# driver-power-stage.net
KiCad netlist of a schematic drawn in Altium Designer
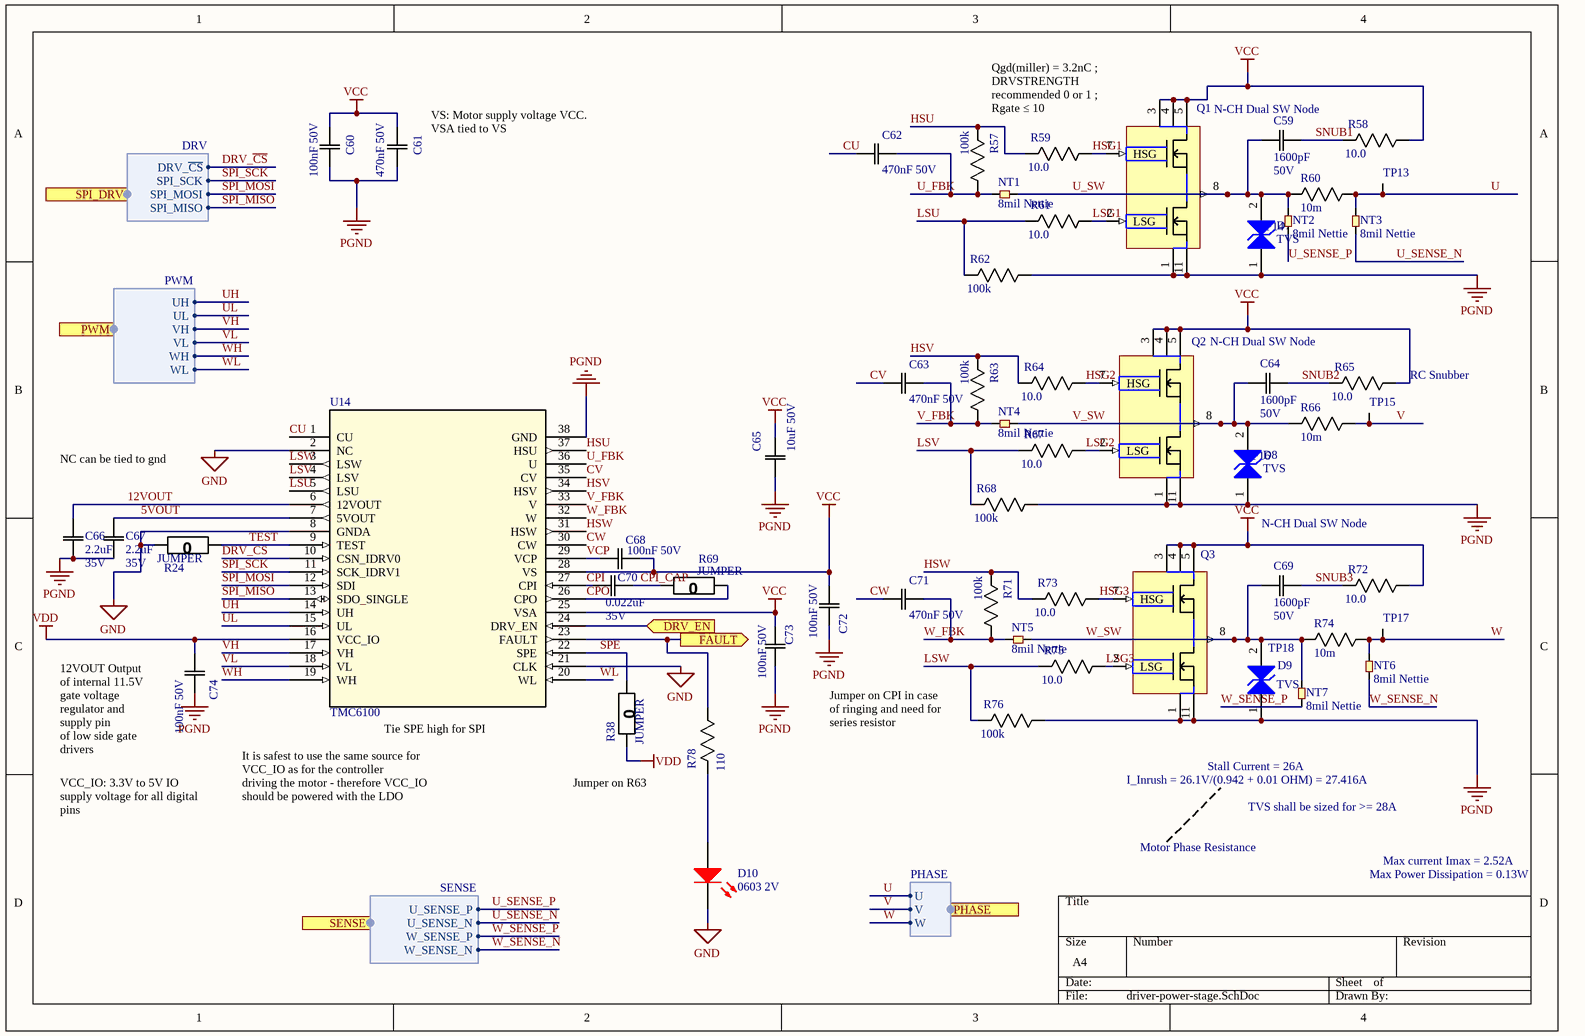
[diagram p0: driver-power-stage.SchDoc]

(export (version "E")
  (design (tool "Eeschema 10.0.6"))
  (components
    (comp (ref "C59")
      (value "1600pF")
      (footprint "0603")
      (description "Default Symbol for Capacitors")
      (fields
        (field (name "TOLERANCE") "5%")
        (field (name "RATING") "50V")
        (field (name "PART NUMBER") "CAP 1600pF 50V")
      )
      (libsource (lib "capacitor_library") (part "CAP_Default"))
    )
    (comp (ref "C60")
      (value "100nF 50V")
      (footprint "0603")
      (description "Default Symbol for Capacitors")
      (fields (field (name "TOLERANCE") "10%") (field (name "PART NUMBER") "CAP 100nF 50V"))
      (libsource (lib "capacitor_library") (part "CAP_Default"))
    )
    (comp (ref "C61")
      (value "470nF 50V")
      (footprint "0603")
      (description "Default Symbol for Capacitors")
      (fields (field (name "TOLERANCE") "10%") (field (name "PART NUMBER") "CAP 470nF 50V"))
      (libsource (lib "capacitor_library") (part "CAP_Default"))
    )
    (comp (ref "C62")
      (value "470nF 50V")
      (footprint "0603")
      (description "Default Symbol for Capacitors")
      (fields (field (name "TOLERANCE") "10%") (field (name "PART NUMBER") "CAP 470nF 50V"))
      (libsource (lib "capacitor_library") (part "CAP_Default"))
    )
    (comp (ref "C63")
      (value "470nF 50V")
      (footprint "0603")
      (description "Default Symbol for Capacitors")
      (fields (field (name "TOLERANCE") "10%") (field (name "PART NUMBER") "CAP 470nF 50V"))
      (libsource (lib "capacitor_library") (part "CAP_Default"))
    )
    (comp (ref "C64")
      (value "1600pF")
      (footprint "0603")
      (description "Default Symbol for Capacitors")
      (fields
        (field (name "TOLERANCE") "5%")
        (field (name "RATING") "50V")
        (field (name "PART NUMBER") "CAP 1600pF 50V")
      )
      (libsource (lib "capacitor_library") (part "CAP_Default"))
    )
    (comp (ref "C65")
      (value "10uF 50V")
      (footprint "0805")
      (description "Default Symbol for Capacitors")
      (fields (field (name "TOLERANCE") "10%") (field (name "PART NUMBER") "CAP 10uF 50V"))
      (libsource (lib "capacitor_library") (part "CAP_Default"))
    )
    (comp (ref "C66")
      (value "2.2uF")
      (footprint "0603")
      (description "Default Symbol for Capacitors")
      (fields
        (field (name "TOLERANCE") "10%")
        (field (name "RATING") "35V")
        (field (name "PART NUMBER") "CAP 2.2uF 35V")
      )
      (libsource (lib "capacitor_library") (part "CAP_Default"))
    )
    (comp (ref "C67")
      (value "2.2uF")
      (footprint "0603")
      (description "Default Symbol for Capacitors")
      (fields
        (field (name "TOLERANCE") "10%")
        (field (name "RATING") "35V")
        (field (name "PART NUMBER") "CAP 2.2uF 35V")
      )
      (libsource (lib "capacitor_library") (part "CAP_Default"))
    )
    (comp (ref "C68")
      (value "100nF 50V")
      (footprint "0603")
      (description "Default Symbol for Capacitors")
      (fields (field (name "TOLERANCE") "10%") (field (name "PART NUMBER") "CAP 100nF 50V"))
      (libsource (lib "capacitor_library") (part "CAP_Default"))
    )
    (comp (ref "C69")
      (value "1600pF")
      (footprint "0603")
      (description "Default Symbol for Capacitors")
      (fields
        (field (name "TOLERANCE") "5%")
        (field (name "RATING") "50V")
        (field (name "PART NUMBER") "CAP 1600pF 50V")
      )
      (libsource (lib "capacitor_library") (part "CAP_Default"))
    )
    (comp (ref "C70")
      (value "0.022uF")
      (footprint "0603")
      (description "Default Symbol for Capacitors")
      (fields
        (field (name "TOLERANCE") "10%")
        (field (name "RATING") "35V")
        (field (name "PART NUMBER") "CAP 0.022uF 35V")
      )
      (libsource (lib "capacitor_library") (part "CAP_Default"))
    )
    (comp (ref "C71")
      (value "470nF 50V")
      (footprint "0603")
      (description "Default Symbol for Capacitors")
      (fields (field (name "TOLERANCE") "10%") (field (name "PART NUMBER") "CAP 470nF 50V"))
      (libsource (lib "capacitor_library") (part "CAP_Default"))
    )
    (comp (ref "C72")
      (value "100nF 50V")
      (footprint "0603")
      (description "Default Symbol for Capacitors")
      (fields (field (name "TOLERANCE") "10%") (field (name "PART NUMBER") "CAP 100nF 50V"))
      (libsource (lib "capacitor_library") (part "CAP_Default"))
    )
    (comp (ref "C73")
      (value "100nF 50V")
      (footprint "0603")
      (description "Default Symbol for Capacitors")
      (fields (field (name "TOLERANCE") "10%") (field (name "PART NUMBER") "CAP 100nF 50V"))
      (libsource (lib "capacitor_library") (part "CAP_Default"))
    )
    (comp (ref "C74")
      (value "100nF 50V")
      (footprint "0603")
      (description "Default Symbol for Capacitors")
      (fields (field (name "TOLERANCE") "10%") (field (name "PART NUMBER") "CAP 100nF 50V"))
      (libsource (lib "capacitor_library") (part "CAP_Default"))
    )
    (comp (ref "D7")
      (value "TVS")
      (footprint "DO-214AC, SMA")
      (description "TVS DIODE 26V 53.5V SMA")
      (fields (field (name "PART NUMBER") "DIODE TVS 26VWM 53.5VC SMA") (field (name "POWER") "400W"))
      (libsource (lib "Diode_Library") (part "DIODE TVS 26VWM 53.5VC SMA"))
    )
    (comp (ref "D8")
      (value "TVS")
      (footprint "DO-214AC, SMA")
      (description "TVS DIODE 26V 53.5V SMA")
      (fields (field (name "PART NUMBER") "DIODE TVS 26VWM 53.5VC SMA") (field (name "POWER") "400W"))
      (libsource (lib "Diode_Library") (part "DIODE TVS 26VWM 53.5VC SMA"))
    )
    (comp (ref "D9")
      (value "TVS")
      (footprint "DO-214AC, SMA")
      (description "TVS DIODE 26V 53.5V SMA")
      (fields (field (name "PART NUMBER") "DIODE TVS 26VWM 53.5VC SMA") (field (name "POWER") "400W"))
      (libsource (lib "Diode_Library") (part "DIODE TVS 26VWM 53.5VC SMA"))
    )
    (comp (ref "D10")
      (value "0603 2V")
      (footprint "0603 - LED2")
      (description "0603 red led alingap 631nm-639nm water clear 18-180mcd 130d")
      (fields (field (name "PART NUMBER") "LED RED SMD 0603"))
      (libsource (lib "Diode_Library") (part "LED RED SMD 0603"))
    )
    (comp (ref "NT1")
      (value "8mil Nettie")
      (footprint "NT_8mil")
      (description "8mil wide nettie")
      (fields (field (name "PART NUMBER") "NT_8"))
      (libsource (lib "") (part "NT_8_1"))
    )
    (comp (ref "NT2")
      (value "8mil Nettie")
      (footprint "NT_8mil")
      (description "8mil wide nettie")
      (fields (field (name "PART NUMBER") "NT_8"))
      (libsource (lib "IC_Library") (part "NT_8"))
    )
    (comp (ref "NT3")
      (value "8mil Nettie")
      (footprint "NT_8mil")
      (description "8mil wide nettie")
      (fields (field (name "PART NUMBER") "NT_8"))
      (libsource (lib "IC_Library") (part "NT_8"))
    )
    (comp (ref "NT4")
      (value "8mil Nettie")
      (footprint "NT_8mil")
      (description "8mil wide nettie")
      (fields (field (name "PART NUMBER") "NT_8"))
      (libsource (lib "") (part "NT_8_1"))
    )
    (comp (ref "NT5")
      (value "8mil Nettie")
      (footprint "NT_8mil")
      (description "8mil wide nettie")
      (fields (field (name "PART NUMBER") "NT_8"))
      (libsource (lib "") (part "NT_8_1"))
    )
    (comp (ref "NT6")
      (value "8mil Nettie")
      (footprint "NT_8mil")
      (description "8mil wide nettie")
      (fields (field (name "PART NUMBER") "NT_8"))
      (libsource (lib "IC_Library") (part "NT_8"))
    )
    (comp (ref "NT7")
      (value "8mil Nettie")
      (footprint "NT_8mil")
      (description "8mil wide nettie")
      (fields (field (name "PART NUMBER") "NT_8"))
      (libsource (lib "IC_Library") (part "NT_8"))
    )
    (comp (ref "Q1")
      (value "N-CH Dual SW Node")
      (footprint "12-PowerWQFN")
      (description "MOSFET N+N COMMON PHASE SW 40V 60A")
      (fields (field (name "PART NUMBER") "MOSFET N-CH DUAL NTTFD4D0N04HLTWG"))
      (libsource (lib "Transistor_Library") (part "MOSFET N-CH DUAL NTTFD4D0N04HLTWG"))
    )
    (comp (ref "Q2")
      (value "N-CH Dual SW Node")
      (footprint "12-PowerWQFN")
      (description "MOSFET N+N COMMON PHASE SW 40V 60A")
      (fields (field (name "PART NUMBER") "MOSFET N-CH DUAL NTTFD4D0N04HLTWG"))
      (libsource (lib "Transistor_Library") (part "MOSFET N-CH DUAL NTTFD4D0N04HLTWG"))
    )
    (comp (ref "Q3")
      (value "N-CH Dual SW Node")
      (footprint "12-PowerWQFN")
      (description "MOSFET N+N COMMON PHASE SW 40V 60A")
      (fields (field (name "PART NUMBER") "MOSFET N-CH DUAL NTTFD4D0N04HLTWG"))
      (libsource (lib "Transistor_Library") (part "MOSFET N-CH DUAL NTTFD4D0N04HLTWG"))
    )
    (comp (ref "R24")
      (value "JUMPER")
      (footprint "0603")
      (description "RES SMD 0 OHM JUMPER GENERIC 0805")
      (fields (field (name "PART NUMBER") "RES 0 JUMPER"))
      (libsource (lib "Resistor_Library") (part "RES 0 JUMPER"))
    )
    (comp (ref "R38")
      (value "JUMPER")
      (footprint "0603")
      (description "RES SMD 0 OHM JUMPER GENERIC 0805")
      (fields (field (name "PART NUMBER") "RES 0 JUMPER"))
      (libsource (lib "Resistor_Library") (part "RES 0 JUMPER"))
    )
    (comp (ref "R57")
      (value "100k")
      (footprint "0603")
      (description "Default Resistor Symbol")
      (fields (field (name "TOLERANCE") "5%") (field (name "PART NUMBER") "RES 100k 1/8W"))
      (libsource (lib "") (part "RES_DEFAULT_1"))
    )
    (comp (ref "R58")
      (value "10.0")
      (footprint "0603")
      (description "Default Resistor Symbol")
      (fields (field (name "TOLERANCE") "1%") (field (name "PART NUMBER") "RES 10.0 1/8W - 1%"))
      (libsource (lib "Resistor_Library") (part "RES_DEFAULT"))
    )
    (comp (ref "R59")
      (value "10.0")
      (footprint "0603")
      (description "Default Resistor Symbol")
      (fields (field (name "TOLERANCE") "1%") (field (name "PART NUMBER") "RES 10.0 1/8W - 1%"))
      (libsource (lib "") (part "RES_DEFAULT_1"))
    )
    (comp (ref "R60")
      (value "10m")
      (footprint "1206")
      (description "Default Resistor Symbol")
      (fields (field (name "TOLERANCE") "1%") (field (name "PART NUMBER") "RES 10m 1W"))
      (libsource (lib "") (part "RES_DEFAULT_1"))
    )
    (comp (ref "R61")
      (value "10.0")
      (footprint "0603")
      (description "Default Resistor Symbol")
      (fields (field (name "TOLERANCE") "1%") (field (name "PART NUMBER") "RES 10.0 1/8W - 1%"))
      (libsource (lib "") (part "RES_DEFAULT_1"))
    )
    (comp (ref "R62")
      (value "100k")
      (footprint "0603")
      (description "Default Resistor Symbol")
      (fields (field (name "TOLERANCE") "5%") (field (name "PART NUMBER") "RES 100k 1/8W"))
      (libsource (lib "") (part "RES_DEFAULT_1"))
    )
    (comp (ref "R63")
      (value "100k")
      (footprint "0603")
      (description "Default Resistor Symbol")
      (fields (field (name "TOLERANCE") "5%") (field (name "PART NUMBER") "RES 100k 1/8W"))
      (libsource (lib "") (part "RES_DEFAULT_1"))
    )
    (comp (ref "R64")
      (value "10.0")
      (footprint "0603")
      (description "Default Resistor Symbol")
      (fields (field (name "TOLERANCE") "1%") (field (name "PART NUMBER") "RES 10.0 1/8W - 1%"))
      (libsource (lib "Resistor_Library") (part "RES_DEFAULT"))
    )
    (comp (ref "R65")
      (value "10.0")
      (footprint "0603")
      (description "Default Resistor Symbol")
      (fields (field (name "TOLERANCE") "1%") (field (name "PART NUMBER") "RES 10.0 1/8W - 1%"))
      (libsource (lib "Resistor_Library") (part "RES_DEFAULT"))
    )
    (comp (ref "R66")
      (value "10m")
      (footprint "1206")
      (description "Default Resistor Symbol")
      (fields (field (name "TOLERANCE") "1%") (field (name "PART NUMBER") "RES 10m 1W"))
      (libsource (lib "Resistor_Library") (part "RES_DEFAULT"))
    )
    (comp (ref "R67")
      (value "10.0")
      (footprint "0603")
      (description "Default Resistor Symbol")
      (fields (field (name "TOLERANCE") "1%") (field (name "PART NUMBER") "RES 10.0 1/8W - 1%"))
      (libsource (lib "") (part "RES_DEFAULT_1"))
    )
    (comp (ref "R68")
      (value "100k")
      (footprint "0603")
      (description "Default Resistor Symbol")
      (fields (field (name "TOLERANCE") "5%") (field (name "PART NUMBER") "RES 100k 1/8W"))
      (libsource (lib "") (part "RES_DEFAULT_1"))
    )
    (comp (ref "R69")
      (value "JUMPER")
      (footprint "0603")
      (description "RES SMD 0 OHM JUMPER GENERIC 0805")
      (fields (field (name "PART NUMBER") "RES 0 JUMPER"))
      (libsource (lib "Resistor_Library") (part "RES 0 JUMPER"))
    )
    (comp (ref "R71")
      (value "100k")
      (footprint "0603")
      (description "Default Resistor Symbol")
      (fields (field (name "TOLERANCE") "5%") (field (name "PART NUMBER") "RES 100k 1/8W"))
      (libsource (lib "") (part "RES_DEFAULT_1"))
    )
    (comp (ref "R72")
      (value "10.0")
      (footprint "0603")
      (description "Default Resistor Symbol")
      (fields (field (name "TOLERANCE") "1%") (field (name "PART NUMBER") "RES 10.0 1/8W - 1%"))
      (libsource (lib "Resistor_Library") (part "RES_DEFAULT"))
    )
    (comp (ref "R73")
      (value "10.0")
      (footprint "0603")
      (description "Default Resistor Symbol")
      (fields (field (name "TOLERANCE") "1%") (field (name "PART NUMBER") "RES 10.0 1/8W - 1%"))
      (libsource (lib "Resistor_Library") (part "RES_DEFAULT"))
    )
    (comp (ref "R74")
      (value "10m")
      (footprint "1206")
      (description "Default Resistor Symbol")
      (fields (field (name "TOLERANCE") "1%") (field (name "PART NUMBER") "RES 10m 1W"))
      (libsource (lib "Resistor_Library") (part "RES_DEFAULT"))
    )
    (comp (ref "R75")
      (value "10.0")
      (footprint "0603")
      (description "Default Resistor Symbol")
      (fields (field (name "TOLERANCE") "1%") (field (name "PART NUMBER") "RES 10.0 1/8W - 1%"))
      (libsource (lib "Resistor_Library") (part "RES_DEFAULT"))
    )
    (comp (ref "R76")
      (value "100k")
      (footprint "0603")
      (description "Default Resistor Symbol")
      (fields (field (name "TOLERANCE") "5%") (field (name "PART NUMBER") "RES 100k 1/8W"))
      (libsource (lib "") (part "RES_DEFAULT_1"))
    )
    (comp (ref "R78")
      (value "110")
      (footprint "0603")
      (description "Default Resistor Symbol")
      (fields (field (name "TOLERANCE") "1%") (field (name "PART NUMBER") "RES 110.0 1/8W - 1%"))
      (libsource (lib "") (part "RES_DEFAULT_1"))
    )
    (comp (ref "TP13")
      (value "Test Point (Via)")
      (footprint "TP")
      (libsource (lib "IC_Library") (part "Test Point (Via)"))
    )
    (comp (ref "TP14")
      (value "Test Point (Via)")
      (footprint "TP")
      (libsource (lib "IC_Library") (part "Test Point (Via)"))
    )
    (comp (ref "TP15")
      (value "Test Point (Via)")
      (footprint "TP")
      (libsource (lib "IC_Library") (part "Test Point (Via)"))
    )
    (comp (ref "TP16")
      (value "Test Point (Via)")
      (footprint "TP")
      (libsource (lib "IC_Library") (part "Test Point (Via)"))
    )
    (comp (ref "TP17")
      (value "Test Point (Via)")
      (footprint "TP")
      (libsource (lib "IC_Library") (part "Test Point (Via)"))
    )
    (comp (ref "TP18")
      (value "Test Point (Via)")
      (footprint "TP")
      (libsource (lib "IC_Library") (part "Test Point (Via)"))
    )
    (comp (ref "U14")
      (value "TMC6100")
      (footprint "QFN50P700X700X85_HS-38N")
      (description "GATE DRIVER IC 8-60V QFN37")
      (libsource (lib "IC_Library") (part "TMC6100"))
    )
  )
  (nets
    (net (code "5") (name "/5VOUT") (class "Default")
      (node (ref "C67") (pin "2") (pinfunction "C2_2") (pintype "passive"))
      (node (ref "U14") (pin "7") (pinfunction "5VOUT_7") (pintype "output"))
    )
    (net (code "6") (name "/12VOUT") (class "Default")
      (node (ref "C66") (pin "2") (pinfunction "C2_2") (pintype "passive"))
      (node (ref "U14") (pin "6") (pinfunction "12VOUT_6") (pintype "output"))
    )
    (net (code "7") (name "/CPI") (class "Default")
      (node (ref "C70") (pin "1") (pinfunction "C1_1") (pintype "passive"))
      (node (ref "U14") (pin "27") (pinfunction "CPI_27") (pintype "input"))
    )
    (net (code "8") (name "/CPI_CAP") (class "Default")
      (node (ref "C70") (pin "2") (pinfunction "C2_2") (pintype "passive"))
      (node (ref "R69") (pin "2") (pinfunction "R2_2") (pintype "passive"))
    )
    (net (code "9") (name "/CPO") (class "Default")
      (node (ref "R69") (pin "1") (pinfunction "R1_1") (pintype "passive"))
      (node (ref "U14") (pin "26") (pinfunction "CPO_26") (pintype "output"))
    )
    (net (code "10") (name "/CU") (class "Default")
      (node (ref "C62") (pin "1") (pinfunction "C1_1") (pintype "passive"))
      (node (ref "U14") (pin "1") (pinfunction "CU_1") (pintype "passive"))
    )
    (net (code "11") (name "/CV") (class "Default")
      (node (ref "C63") (pin "1") (pinfunction "C1_1") (pintype "passive"))
      (node (ref "U14") (pin "35") (pinfunction "CV_35") (pintype "passive"))
    )
    (net (code "12") (name "/CW") (class "Default")
      (node (ref "C71") (pin "1") (pinfunction "C1_1") (pintype "passive"))
      (node (ref "U14") (pin "30") (pinfunction "CW_30") (pintype "passive"))
    )
    (net (code "13") (name "/DRV_EN") (class "Default")
      (node (ref "U14") (pin "24") (pinfunction "DRV_EN_24") (pintype "input"))
    )
    (net (code "14") (name "/DRV_~{CS}") (class "Default")
      (node (ref "U14") (pin "10") (pinfunction "CSN_IDRV0_10") (pintype "input"))
    )
    (net (code "15") (name "/FAULT") (class "Default")
      (node (ref "R78") (pin "1") (pinfunction "R1_1") (pintype "passive"))
      (node (ref "U14") (pin "23") (pinfunction "FAULT_23") (pintype "output"))
    )
    (net (code "16") (name "/HSG1") (class "Default")
      (node (ref "Q1") (pin "7") (pinfunction "HSG_7") (pintype "input"))
      (node (ref "R59") (pin "1") (pinfunction "R1_1") (pintype "passive"))
    )
    (net (code "17") (name "/HSG2") (class "Default")
      (node (ref "Q2") (pin "7") (pinfunction "HSG_7") (pintype "input"))
      (node (ref "R64") (pin "1") (pinfunction "R1_1") (pintype "passive"))
    )
    (net (code "18") (name "/HSG3") (class "Default")
      (node (ref "Q3") (pin "7") (pinfunction "HSG_7") (pintype "input"))
      (node (ref "R73") (pin "1") (pinfunction "R1_1") (pintype "passive"))
    )
    (net (code "19") (name "/HSU") (class "Default")
      (node (ref "R57") (pin "2") (pinfunction "R2_2") (pintype "passive"))
      (node (ref "R59") (pin "2") (pinfunction "R2_2") (pintype "passive"))
      (node (ref "U14") (pin "37") (pinfunction "HSU_37") (pintype "output"))
    )
    (net (code "20") (name "/HSV") (class "Default")
      (node (ref "R63") (pin "2") (pinfunction "R2_2") (pintype "passive"))
      (node (ref "R64") (pin "2") (pinfunction "R2_2") (pintype "passive"))
      (node (ref "U14") (pin "34") (pinfunction "HSV_34") (pintype "output"))
    )
    (net (code "21") (name "/HSW") (class "Default")
      (node (ref "R71") (pin "2") (pinfunction "R2_2") (pintype "passive"))
      (node (ref "R73") (pin "2") (pinfunction "R2_2") (pintype "passive"))
      (node (ref "U14") (pin "31") (pinfunction "HSW_31") (pintype "output"))
    )
    (net (code "22") (name "/LSG1") (class "Default")
      (node (ref "Q1") (pin "2") (pinfunction "LSG_2") (pintype "input"))
      (node (ref "R61") (pin "1") (pinfunction "R1_1") (pintype "passive"))
    )
    (net (code "23") (name "/LSG2") (class "Default")
      (node (ref "Q2") (pin "2") (pinfunction "LSG_2") (pintype "input"))
      (node (ref "R67") (pin "1") (pinfunction "R1_1") (pintype "passive"))
    )
    (net (code "24") (name "/LSG3") (class "Default")
      (node (ref "Q3") (pin "2") (pinfunction "LSG_2") (pintype "input"))
      (node (ref "R75") (pin "1") (pinfunction "R1_1") (pintype "passive"))
    )
    (net (code "25") (name "/LSU") (class "Default")
      (node (ref "R61") (pin "2") (pinfunction "R2_2") (pintype "passive"))
      (node (ref "R62") (pin "2") (pinfunction "R2_2") (pintype "passive"))
      (node (ref "U14") (pin "5") (pinfunction "LSU_5") (pintype "output"))
    )
    (net (code "26") (name "/LSV") (class "Default")
      (node (ref "R67") (pin "2") (pinfunction "R2_2") (pintype "passive"))
      (node (ref "R68") (pin "2") (pinfunction "R2_2") (pintype "passive"))
      (node (ref "U14") (pin "4") (pinfunction "LSV_4") (pintype "output"))
    )
    (net (code "27") (name "/LSW") (class "Default")
      (node (ref "R75") (pin "2") (pinfunction "R2_2") (pintype "passive"))
      (node (ref "R76") (pin "2") (pinfunction "R2_2") (pintype "passive"))
      (node (ref "U14") (pin "3") (pinfunction "LSW_3") (pintype "output"))
    )
    (net (code "28") (name "/SNUB1") (class "Default")
      (node (ref "C59") (pin "1") (pinfunction "C1_1") (pintype "passive"))
      (node (ref "R58") (pin "2") (pinfunction "R2_2") (pintype "passive"))
    )
    (net (code "29") (name "/SNUB2") (class "Default")
      (node (ref "C64") (pin "1") (pinfunction "C1_1") (pintype "passive"))
      (node (ref "R65") (pin "2") (pinfunction "R2_2") (pintype "passive"))
    )
    (net (code "30") (name "/SNUB3") (class "Default")
      (node (ref "C69") (pin "1") (pinfunction "C1_1") (pintype "passive"))
      (node (ref "R72") (pin "2") (pinfunction "R2_2") (pintype "passive"))
    )
    (net (code "31") (name "/SPE") (class "Default")
      (node (ref "R38") (pin "1") (pinfunction "R1_1") (pintype "passive"))
      (node (ref "U14") (pin "22") (pinfunction "SPE_22") (pintype "input"))
    )
    (net (code "32") (name "/SPI_MISO") (class "Default")
      (node (ref "U14") (pin "13") (pinfunction "SDO_SINGLE_13") (pintype "bidirectional"))
    )
    (net (code "33") (name "/SPI_MOSI") (class "Default")
      (node (ref "U14") (pin "12") (pinfunction "SDI_12") (pintype "input"))
    )
    (net (code "34") (name "/SPI_SCK") (class "Default")
      (node (ref "U14") (pin "11") (pinfunction "SCK_IDRV1_11") (pintype "input"))
    )
    (net (code "35") (name "/TEST") (class "Default")
      (node (ref "R24") (pin "1") (pinfunction "R1_1") (pintype "passive"))
      (node (ref "U14") (pin "9") (pinfunction "TEST_9") (pintype "input"))
    )
    (net (code "36") (name "/U") (class "Default")
      (node (ref "NT3") (pin "2") (pinfunction "2_2") (pintype "passive"))
      (node (ref "R60") (pin "1") (pinfunction "R1_1") (pintype "passive"))
      (node (ref "TP13") (pin "1") (pinfunction "1_1") (pintype "passive"))
    )
    (net (code "37") (name "/UH") (class "Default")
      (node (ref "U14") (pin "14") (pinfunction "UH_14") (pintype "input"))
    )
    (net (code "38") (name "/UL") (class "Default")
      (node (ref "U14") (pin "15") (pinfunction "UL_15") (pintype "input"))
    )
    (net (code "39") (name "/U_FBK") (class "Default")
      (node (ref "C62") (pin "2") (pinfunction "C2_2") (pintype "passive"))
      (node (ref "NT1") (pin "2") (pinfunction "2_2") (pintype "passive"))
      (node (ref "R57") (pin "1") (pinfunction "R1_1") (pintype "passive"))
      (node (ref "U14") (pin "36") (pinfunction "U_36") (pintype "passive"))
    )
    (net (code "40") (name "/U_SENSE_N") (class "Default")
      (node (ref "NT3") (pin "1") (pinfunction "1_1") (pintype "passive"))
    )
    (net (code "41") (name "/U_SENSE_P") (class "Default")
      (node (ref "NT2") (pin "1") (pinfunction "1_1") (pintype "passive"))
    )
    (net (code "42") (name "/U_SW") (class "Default")
      (node (ref "C59") (pin "2") (pinfunction "C2_2") (pintype "passive"))
      (node (ref "D7") (pin "2") (pinfunction "A_2") (pintype "passive"))
      (node (ref "NT1") (pin "1") (pinfunction "1_1") (pintype "passive"))
      (node (ref "NT2") (pin "2") (pinfunction "2_2") (pintype "passive"))
      (node (ref "Q1") (pin "8") (pinfunction "SW_8") (pintype "output"))
      (node (ref "R60") (pin "2") (pinfunction "R2_2") (pintype "passive"))
      (node (ref "TP14") (pin "1") (pinfunction "1_1") (pintype "passive"))
    )
    (net (code "43") (name "/V") (class "Default")
      (node (ref "R66") (pin "1") (pinfunction "R1_1") (pintype "passive"))
      (node (ref "TP15") (pin "1") (pinfunction "1_1") (pintype "passive"))
    )
    (net (code "44") (name "/VCP") (class "Default")
      (node (ref "C68") (pin "1") (pinfunction "C1_1") (pintype "passive"))
      (node (ref "U14") (pin "29") (pinfunction "VCP_29") (pintype "power_in"))
    )
    (net (code "45") (name "/VH") (class "Default")
      (node (ref "U14") (pin "17") (pinfunction "VH_17") (pintype "input"))
    )
    (net (code "46") (name "/VL") (class "Default")
      (node (ref "U14") (pin "18") (pinfunction "VL_18") (pintype "input"))
    )
    (net (code "47") (name "/V_FBK") (class "Default")
      (node (ref "C63") (pin "2") (pinfunction "C2_2") (pintype "passive"))
      (node (ref "NT4") (pin "2") (pinfunction "2_2") (pintype "passive"))
      (node (ref "R63") (pin "1") (pinfunction "R1_1") (pintype "passive"))
      (node (ref "U14") (pin "33") (pinfunction "V_33") (pintype "passive"))
    )
    (net (code "48") (name "/V_SW") (class "Default")
      (node (ref "C64") (pin "2") (pinfunction "C2_2") (pintype "passive"))
      (node (ref "D8") (pin "2") (pinfunction "A_2") (pintype "passive"))
      (node (ref "NT4") (pin "1") (pinfunction "1_1") (pintype "passive"))
      (node (ref "Q2") (pin "8") (pinfunction "SW_8") (pintype "output"))
      (node (ref "R66") (pin "2") (pinfunction "R2_2") (pintype "passive"))
      (node (ref "TP16") (pin "1") (pinfunction "1_1") (pintype "passive"))
    )
    (net (code "49") (name "/W") (class "Default")
      (node (ref "NT6") (pin "2") (pinfunction "2_2") (pintype "passive"))
      (node (ref "R74") (pin "1") (pinfunction "R1_1") (pintype "passive"))
      (node (ref "TP17") (pin "1") (pinfunction "1_1") (pintype "passive"))
    )
    (net (code "50") (name "/WH") (class "Default")
      (node (ref "U14") (pin "19") (pinfunction "WH_19") (pintype "input"))
    )
    (net (code "51") (name "/WL") (class "Default")
      (node (ref "U14") (pin "20") (pinfunction "WL_20") (pintype "input"))
    )
    (net (code "52") (name "/W_FBK") (class "Default")
      (node (ref "C71") (pin "2") (pinfunction "C2_2") (pintype "passive"))
      (node (ref "NT5") (pin "2") (pinfunction "2_2") (pintype "passive"))
      (node (ref "R71") (pin "1") (pinfunction "R1_1") (pintype "passive"))
      (node (ref "U14") (pin "32") (pinfunction "W_32") (pintype "passive"))
    )
    (net (code "53") (name "/W_SENSE_N") (class "Default")
      (node (ref "NT6") (pin "1") (pinfunction "1_1") (pintype "passive"))
    )
    (net (code "54") (name "/W_SENSE_P") (class "Default")
      (node (ref "NT7") (pin "1") (pinfunction "1_1") (pintype "passive"))
    )
    (net (code "55") (name "/W_SW") (class "Default")
      (node (ref "C69") (pin "2") (pinfunction "C2_2") (pintype "passive"))
      (node (ref "D9") (pin "2") (pinfunction "A_2") (pintype "passive"))
      (node (ref "NT5") (pin "1") (pinfunction "1_1") (pintype "passive"))
      (node (ref "NT7") (pin "2") (pinfunction "2_2") (pintype "passive"))
      (node (ref "Q3") (pin "8") (pinfunction "SW_8") (pintype "output"))
      (node (ref "R74") (pin "2") (pinfunction "R2_2") (pintype "passive"))
      (node (ref "TP18") (pin "1") (pinfunction "1_1") (pintype "passive"))
    )
    (net (code "60") (name "GND") (class "Default")
      (node (ref "D10") (pin "2") (pinfunction "K_2") (pintype "passive"))
      (node (ref "R24") (pin "2") (pinfunction "R2_2") (pintype "passive"))
      (node (ref "U14") (pin "2") (pinfunction "NC_2") (pintype "passive"))
      (node (ref "U14") (pin "21") (pinfunction "CLK_21") (pintype "input"))
      (node (ref "U14") (pin "8") (pinfunction "GNDA_8") (pintype "power_in"))
    )
    (net (code "61") (name "Net-(D10-A)") (class "Default")
      (node (ref "D10") (pin "1") (pinfunction "A_1") (pintype "passive"))
      (node (ref "R78") (pin "2") (pinfunction "R2_2") (pintype "passive"))
    )
    (net (code "62") (name "PGND") (class "Default")
      (node (ref "C60") (pin "2") (pinfunction "C2_2") (pintype "passive"))
      (node (ref "C61") (pin "2") (pinfunction "C2_2") (pintype "passive"))
      (node (ref "C65") (pin "1") (pinfunction "C1_1") (pintype "passive"))
      (node (ref "C66") (pin "1") (pinfunction "C1_1") (pintype "passive"))
      (node (ref "C67") (pin "1") (pinfunction "C1_1") (pintype "passive"))
      (node (ref "C72") (pin "2") (pinfunction "C2_2") (pintype "passive"))
      (node (ref "C73") (pin "2") (pinfunction "C2_2") (pintype "passive"))
      (node (ref "C74") (pin "2") (pinfunction "C2_2") (pintype "passive"))
      (node (ref "D7") (pin "1") (pinfunction "K_1") (pintype "passive"))
      (node (ref "D8") (pin "1") (pinfunction "K_1") (pintype "passive"))
      (node (ref "D9") (pin "1") (pinfunction "K_1") (pintype "passive"))
      (node (ref "Q1") (pin "1") (pinfunction "GND_1") (pintype "power_in"))
      (node (ref "Q1") (pin "11") (pinfunction "GND_11") (pintype "power_in"))
      (node (ref "Q2") (pin "1") (pinfunction "GND_1") (pintype "power_in"))
      (node (ref "Q2") (pin "11") (pinfunction "GND_11") (pintype "power_in"))
      (node (ref "Q3") (pin "1") (pinfunction "GND_1") (pintype "power_in"))
      (node (ref "Q3") (pin "11") (pinfunction "GND_11") (pintype "power_in"))
      (node (ref "R62") (pin "1") (pinfunction "R1_1") (pintype "passive"))
      (node (ref "R68") (pin "1") (pinfunction "R1_1") (pintype "passive"))
      (node (ref "R76") (pin "1") (pinfunction "R1_1") (pintype "passive"))
      (node (ref "U14") (pin "38") (pinfunction "GND_38") (pintype "passive"))
    )
    (net (code "63") (name "VCC") (class "Default")
      (node (ref "C60") (pin "1") (pinfunction "C1_1") (pintype "passive"))
      (node (ref "C61") (pin "1") (pinfunction "C1_1") (pintype "passive"))
      (node (ref "C65") (pin "2") (pinfunction "C2_2") (pintype "passive"))
      (node (ref "C68") (pin "2") (pinfunction "C2_2") (pintype "passive"))
      (node (ref "C72") (pin "1") (pinfunction "C1_1") (pintype "passive"))
      (node (ref "C73") (pin "1") (pinfunction "C1_1") (pintype "passive"))
      (node (ref "Q1") (pin "3") (pinfunction "V+_3") (pintype "power_in"))
      (node (ref "Q1") (pin "4") (pinfunction "V+_4") (pintype "power_in"))
      (node (ref "Q1") (pin "5") (pinfunction "V+_5") (pintype "power_in"))
      (node (ref "Q2") (pin "3") (pinfunction "V+_3") (pintype "power_in"))
      (node (ref "Q2") (pin "4") (pinfunction "V+_4") (pintype "power_in"))
      (node (ref "Q2") (pin "5") (pinfunction "V+_5") (pintype "power_in"))
      (node (ref "Q3") (pin "3") (pinfunction "V+_3") (pintype "power_in"))
      (node (ref "Q3") (pin "4") (pinfunction "V+_4") (pintype "power_in"))
      (node (ref "Q3") (pin "5") (pinfunction "V+_5") (pintype "power_in"))
      (node (ref "R58") (pin "1") (pinfunction "R1_1") (pintype "passive"))
      (node (ref "R65") (pin "1") (pinfunction "R1_1") (pintype "passive"))
      (node (ref "R72") (pin "1") (pinfunction "R1_1") (pintype "passive"))
      (node (ref "U14") (pin "25") (pinfunction "VSA_25") (pintype "power_in"))
      (node (ref "U14") (pin "28") (pinfunction "VS_28") (pintype "power_in"))
    )
    (net (code "64") (name "VDD") (class "Default")
      (node (ref "C74") (pin "1") (pinfunction "C1_1") (pintype "passive"))
      (node (ref "R38") (pin "2") (pinfunction "R2_2") (pintype "passive"))
      (node (ref "U14") (pin "16") (pinfunction "VCC_IO_16") (pintype "power_in"))
    )
  )
)
